# Display_connection.net
KiCad netlist of a schematic drawn in EAGLE
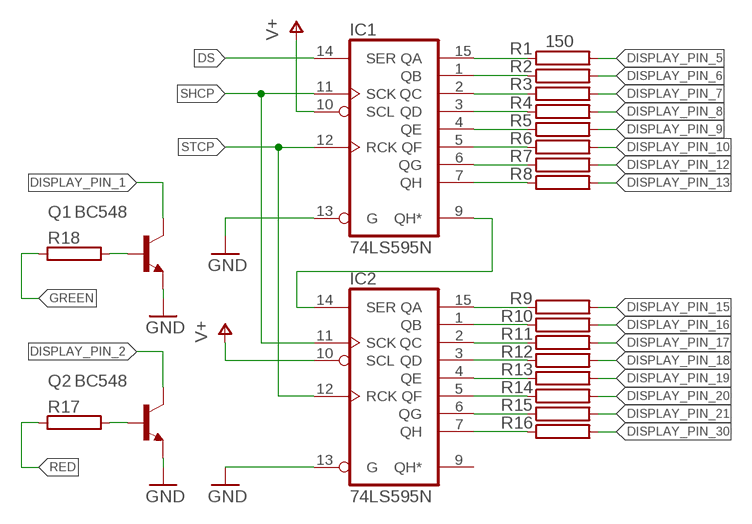
[diagram p0: schematic, sheet 1]

(export (version "E")
  (design (tool "Eeschema 10.0.6"))
  (components
    (comp (ref "IC1")
      (value "74LS595N")
      (footprint "eagle-import:DIL16")
      (libsource (lib "eagle-import") (part "74595NLS"))
    )
    (comp (ref "IC2")
      (value "74LS595N")
      (footprint "eagle-import:DIL16")
      (libsource (lib "eagle-import") (part "74595NLS"))
    )
    (comp (ref "Q1")
      (value "BC548")
      (footprint "eagle-import:TO92-EBC")
      (libsource (lib "eagle-import") (part "BC548"))
    )
    (comp (ref "Q2")
      (value "BC548")
      (footprint "eagle-import:TO92-EBC")
      (libsource (lib "eagle-import") (part "BC548"))
    )
    (comp (ref "R1")
      (value "150")
      (footprint "eagle-import:CA0002")
      (libsource (lib "eagle-import") (part "RCA0002"))
    )
    (comp (ref "R2")
      (value "RCA0002")
      (footprint "eagle-import:CA0002")
      (libsource (lib "eagle-import") (part "RCA0002"))
    )
    (comp (ref "R3")
      (value "RCA0002")
      (footprint "eagle-import:CA0002")
      (libsource (lib "eagle-import") (part "RCA0002"))
    )
    (comp (ref "R4")
      (value "RCA0002")
      (footprint "eagle-import:CA0002")
      (libsource (lib "eagle-import") (part "RCA0002"))
    )
    (comp (ref "R5")
      (value "RCA0002")
      (footprint "eagle-import:CA0002")
      (libsource (lib "eagle-import") (part "RCA0002"))
    )
    (comp (ref "R6")
      (value "RCA0002")
      (footprint "eagle-import:CA0002")
      (libsource (lib "eagle-import") (part "RCA0002"))
    )
    (comp (ref "R7")
      (value "RCA0002")
      (footprint "eagle-import:CA0002")
      (libsource (lib "eagle-import") (part "RCA0002"))
    )
    (comp (ref "R8")
      (value "RCA0002")
      (footprint "eagle-import:CA0002")
      (libsource (lib "eagle-import") (part "RCA0002"))
    )
    (comp (ref "R9")
      (value "RCA0002")
      (footprint "eagle-import:CA0002")
      (libsource (lib "eagle-import") (part "RCA0002"))
    )
    (comp (ref "R10")
      (value "RCA0002")
      (footprint "eagle-import:CA0002")
      (libsource (lib "eagle-import") (part "RCA0002"))
    )
    (comp (ref "R11")
      (value "RCA0002")
      (footprint "eagle-import:CA0002")
      (libsource (lib "eagle-import") (part "RCA0002"))
    )
    (comp (ref "R12")
      (value "RCA0002")
      (footprint "eagle-import:CA0002")
      (libsource (lib "eagle-import") (part "RCA0002"))
    )
    (comp (ref "R13")
      (value "RCA0002")
      (footprint "eagle-import:CA0002")
      (libsource (lib "eagle-import") (part "RCA0002"))
    )
    (comp (ref "R14")
      (value "RCA0002")
      (footprint "eagle-import:CA0002")
      (libsource (lib "eagle-import") (part "RCA0002"))
    )
    (comp (ref "R15")
      (value "RCA0002")
      (footprint "eagle-import:CA0002")
      (libsource (lib "eagle-import") (part "RCA0002"))
    )
    (comp (ref "R16")
      (value "RCA0002")
      (footprint "eagle-import:CA0002")
      (libsource (lib "eagle-import") (part "RCA0002"))
    )
    (comp (ref "R17")
      (value "RCA0002")
      (footprint "eagle-import:CA0002")
      (libsource (lib "eagle-import") (part "RCA0002"))
    )
    (comp (ref "R18")
      (value "RCA0002")
      (footprint "eagle-import:CA0002")
      (libsource (lib "eagle-import") (part "RCA0002"))
    )
  )
  (nets
    (net (code "1") (name "DISPLAY_PIN_1") (class "Default")
      (node (ref "Q1") (pin "C") (pinfunction "C_C") (pintype "passive"))
    )
    (net (code "2") (name "DISPLAY_PIN_2") (class "Default")
      (node (ref "Q2") (pin "C") (pinfunction "C_C") (pintype "passive"))
    )
    (net (code "3") (name "DISPLAY_PIN_5") (class "Default")
      (node (ref "R1") (pin "2") (pinfunction "2_2") (pintype "passive"))
    )
    (net (code "4") (name "DISPLAY_PIN_6") (class "Default")
      (node (ref "R2") (pin "2") (pinfunction "2_2") (pintype "passive"))
    )
    (net (code "5") (name "DISPLAY_PIN_7") (class "Default")
      (node (ref "R3") (pin "2") (pinfunction "2_2") (pintype "passive"))
    )
    (net (code "6") (name "DISPLAY_PIN_8") (class "Default")
      (node (ref "R4") (pin "2") (pinfunction "2_2") (pintype "passive"))
    )
    (net (code "7") (name "DISPLAY_PIN_9") (class "Default")
      (node (ref "R5") (pin "2") (pinfunction "2_2") (pintype "passive"))
    )
    (net (code "8") (name "DISPLAY_PIN_10") (class "Default")
      (node (ref "R6") (pin "2") (pinfunction "2_2") (pintype "passive"))
    )
    (net (code "9") (name "DISPLAY_PIN_12") (class "Default")
      (node (ref "R7") (pin "2") (pinfunction "2_2") (pintype "passive"))
    )
    (net (code "10") (name "DISPLAY_PIN_13") (class "Default")
      (node (ref "R8") (pin "2") (pinfunction "2_2") (pintype "passive"))
    )
    (net (code "11") (name "DISPLAY_PIN_15") (class "Default")
      (node (ref "R9") (pin "2") (pinfunction "2_2") (pintype "passive"))
    )
    (net (code "12") (name "DISPLAY_PIN_16") (class "Default")
      (node (ref "R10") (pin "2") (pinfunction "2_2") (pintype "passive"))
    )
    (net (code "13") (name "DISPLAY_PIN_17") (class "Default")
      (node (ref "R11") (pin "2") (pinfunction "2_2") (pintype "passive"))
    )
    (net (code "14") (name "DISPLAY_PIN_18") (class "Default")
      (node (ref "R12") (pin "2") (pinfunction "2_2") (pintype "passive"))
    )
    (net (code "15") (name "DISPLAY_PIN_19") (class "Default")
      (node (ref "R13") (pin "2") (pinfunction "2_2") (pintype "passive"))
    )
    (net (code "16") (name "DISPLAY_PIN_20") (class "Default")
      (node (ref "R14") (pin "2") (pinfunction "2_2") (pintype "passive"))
    )
    (net (code "17") (name "DISPLAY_PIN_21") (class "Default")
      (node (ref "R15") (pin "2") (pinfunction "2_2") (pintype "passive"))
    )
    (net (code "18") (name "DISPLAY_PIN_30") (class "Default")
      (node (ref "R16") (pin "2") (pinfunction "2_2") (pintype "passive"))
    )
    (net (code "19") (name "DS") (class "Default")
      (node (ref "IC1") (pin "14") (pinfunction "SER_14") (pintype "input"))
    )
    (net (code "20") (name "GND") (class "Default")
      (node (ref "IC1") (pin "13") (pinfunction "G_13") (pintype "input"))
      (node (ref "IC2") (pin "13") (pinfunction "G_13") (pintype "input"))
      (node (ref "Q1") (pin "E") (pinfunction "E_E") (pintype "passive"))
      (node (ref "Q2") (pin "E") (pinfunction "E_E") (pintype "passive"))
    )
    (net (code "21") (name "GREEN") (class "Default")
      (node (ref "R18") (pin "1") (pinfunction "1_1") (pintype "passive"))
    )
    (net (code "22") (name "Net-(IC1A-QA)") (class "Default")
      (node (ref "IC1") (pin "15") (pinfunction "QA_15") (pintype "tri_state"))
      (node (ref "R1") (pin "1") (pinfunction "1_1") (pintype "passive"))
    )
    (net (code "23") (name "Net-(IC1A-QB)") (class "Default")
      (node (ref "IC1") (pin "1") (pinfunction "QB_1") (pintype "tri_state"))
      (node (ref "R2") (pin "1") (pinfunction "1_1") (pintype "passive"))
    )
    (net (code "24") (name "Net-(IC1A-QC)") (class "Default")
      (node (ref "IC1") (pin "2") (pinfunction "QC_2") (pintype "tri_state"))
      (node (ref "R3") (pin "1") (pinfunction "1_1") (pintype "passive"))
    )
    (net (code "25") (name "Net-(IC1A-QD)") (class "Default")
      (node (ref "IC1") (pin "3") (pinfunction "QD_3") (pintype "tri_state"))
      (node (ref "R4") (pin "1") (pinfunction "1_1") (pintype "passive"))
    )
    (net (code "26") (name "Net-(IC1A-QE)") (class "Default")
      (node (ref "IC1") (pin "4") (pinfunction "QE_4") (pintype "tri_state"))
      (node (ref "R5") (pin "1") (pinfunction "1_1") (pintype "passive"))
    )
    (net (code "27") (name "Net-(IC1A-QF)") (class "Default")
      (node (ref "IC1") (pin "5") (pinfunction "QF_5") (pintype "tri_state"))
      (node (ref "R6") (pin "1") (pinfunction "1_1") (pintype "passive"))
    )
    (net (code "28") (name "Net-(IC1A-QG)") (class "Default")
      (node (ref "IC1") (pin "6") (pinfunction "QG_6") (pintype "tri_state"))
      (node (ref "R7") (pin "1") (pinfunction "1_1") (pintype "passive"))
    )
    (net (code "29") (name "Net-(IC1A-QH)") (class "Default")
      (node (ref "IC1") (pin "7") (pinfunction "QH_7") (pintype "tri_state"))
      (node (ref "R8") (pin "1") (pinfunction "1_1") (pintype "passive"))
    )
    (net (code "30") (name "Net-(IC1A-QH*)") (class "Default")
      (node (ref "IC1") (pin "9") (pinfunction "QH*_9") (pintype "tri_state"))
      (node (ref "IC2") (pin "14") (pinfunction "SER_14") (pintype "input"))
    )
    (net (code "31") (name "Net-(IC2A-QA)") (class "Default")
      (node (ref "IC2") (pin "15") (pinfunction "QA_15") (pintype "tri_state"))
      (node (ref "R9") (pin "1") (pinfunction "1_1") (pintype "passive"))
    )
    (net (code "32") (name "Net-(IC2A-QB)") (class "Default")
      (node (ref "IC2") (pin "1") (pinfunction "QB_1") (pintype "tri_state"))
      (node (ref "R10") (pin "1") (pinfunction "1_1") (pintype "passive"))
    )
    (net (code "33") (name "Net-(IC2A-QC)") (class "Default")
      (node (ref "IC2") (pin "2") (pinfunction "QC_2") (pintype "tri_state"))
      (node (ref "R11") (pin "1") (pinfunction "1_1") (pintype "passive"))
    )
    (net (code "34") (name "Net-(IC2A-QD)") (class "Default")
      (node (ref "IC2") (pin "3") (pinfunction "QD_3") (pintype "tri_state"))
      (node (ref "R12") (pin "1") (pinfunction "1_1") (pintype "passive"))
    )
    (net (code "35") (name "Net-(IC2A-QE)") (class "Default")
      (node (ref "IC2") (pin "4") (pinfunction "QE_4") (pintype "tri_state"))
      (node (ref "R13") (pin "1") (pinfunction "1_1") (pintype "passive"))
    )
    (net (code "36") (name "Net-(IC2A-QF)") (class "Default")
      (node (ref "IC2") (pin "5") (pinfunction "QF_5") (pintype "tri_state"))
      (node (ref "R14") (pin "1") (pinfunction "1_1") (pintype "passive"))
    )
    (net (code "37") (name "Net-(IC2A-QG)") (class "Default")
      (node (ref "IC2") (pin "6") (pinfunction "QG_6") (pintype "tri_state"))
      (node (ref "R15") (pin "1") (pinfunction "1_1") (pintype "passive"))
    )
    (net (code "38") (name "Net-(IC2A-QH)") (class "Default")
      (node (ref "IC2") (pin "7") (pinfunction "QH_7") (pintype "tri_state"))
      (node (ref "R16") (pin "1") (pinfunction "1_1") (pintype "passive"))
    )
    (net (code "39") (name "Net-(Q1-PadB)") (class "Default")
      (node (ref "Q1") (pin "B") (pinfunction "B_B") (pintype "passive"))
      (node (ref "R18") (pin "2") (pinfunction "2_2") (pintype "passive"))
    )
    (net (code "40") (name "Net-(Q2-PadB)") (class "Default")
      (node (ref "Q2") (pin "B") (pinfunction "B_B") (pintype "passive"))
      (node (ref "R17") (pin "2") (pinfunction "2_2") (pintype "passive"))
    )
    (net (code "41") (name "RED") (class "Default")
      (node (ref "R17") (pin "1") (pinfunction "1_1") (pintype "passive"))
    )
    (net (code "42") (name "SHCP") (class "Default")
      (node (ref "IC1") (pin "11") (pinfunction "SCK_11") (pintype "input"))
      (node (ref "IC2") (pin "11") (pinfunction "SCK_11") (pintype "input"))
    )
    (net (code "43") (name "STCP") (class "Default")
      (node (ref "IC1") (pin "12") (pinfunction "RCK_12") (pintype "input"))
      (node (ref "IC2") (pin "12") (pinfunction "RCK_12") (pintype "input"))
    )
    (net (code "44") (name "V+") (class "Default")
      (node (ref "IC1") (pin "10") (pinfunction "SCL_10") (pintype "input"))
      (node (ref "IC2") (pin "10") (pinfunction "SCL_10") (pintype "input"))
    )
    (net (code "45") (name "unconnected-(IC2A-QH*-Pad9)") (class "Default")
      (node (ref "IC2") (pin "9") (pinfunction "QH*_9") (pintype "tri_state"))
    )
  )
)
